# SensorControl.net
KiCad netlist of a schematic drawn in Altium Designer
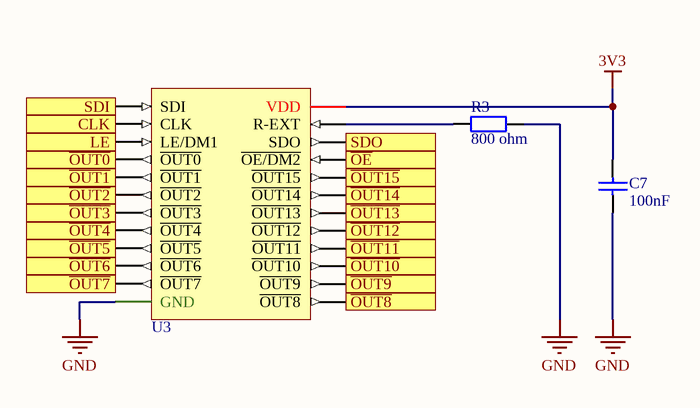
[diagram p0: SensorControl.SchDoc]

(export (version "E")
  (design (tool "Eeschema 10.0.6"))
  (components
    (comp (ref "C7")
      (value "100nF")
      (footprint "FP_0805_CAP_085")
      (description "Capacitor")
      (fields (field (name "TOLERANCE") "+80%/-20%") (field (name "VOLTAGE") "25V"))
      (libsource (lib "hallglib") (part "CAP 100nF"))
    )
    (comp (ref "R3")
      (value "CRCW0805806RFKEA")
      (footprint "0805-W")
      (description "RES, THICK FILM, 806R, 1%, 0.125W, 0805")
      (fields (field (name "RESISTANCE") "800 ohm"))
      (libsource (lib "RobonAUT") (part "CRCW0805806RFKEA"))
    )
    (comp (ref "U3")
      (value "STP16CP05TTR")
      (footprint "24-Pin TSSOP")
      (description "Led Driver, 16 Outputs, Constant Current, 3V-5.5V in, 30MHz switch, 20V/100mA out, TSSOP-24")
      (libsource (lib "RobonAUT") (part "STP16CP05TTR"))
    )
  )
  (nets
    (net (code "1") (name "/CLK") (class "Default")
      (node (ref "U3") (pin "3") (pinfunction "CLK_3") (pintype "input"))
    )
    (net (code "2") (name "/LE") (class "Default")
      (node (ref "U3") (pin "4") (pinfunction "LE/DM1_4") (pintype "input"))
    )
    (net (code "3") (name "/SDI") (class "Default")
      (node (ref "U3") (pin "2") (pinfunction "SDI_2") (pintype "input"))
    )
    (net (code "4") (name "/SDO") (class "Default")
      (node (ref "U3") (pin "22") (pinfunction "SDO_22") (pintype "output"))
    )
    (net (code "5") (name "/~{OE}") (class "Default")
      (node (ref "U3") (pin "21") (pinfunction "~{OE/DM2}_21") (pintype "input"))
    )
    (net (code "6") (name "/~{OUT0}") (class "Default")
      (node (ref "U3") (pin "5") (pinfunction "~{OUT0}_5") (pintype "output"))
    )
    (net (code "7") (name "/~{OUT1}") (class "Default")
      (node (ref "U3") (pin "6") (pinfunction "~{OUT1}_6") (pintype "output"))
    )
    (net (code "8") (name "/~{OUT2}") (class "Default")
      (node (ref "U3") (pin "7") (pinfunction "~{OUT2}_7") (pintype "output"))
    )
    (net (code "9") (name "/~{OUT3}") (class "Default")
      (node (ref "U3") (pin "8") (pinfunction "~{OUT3}_8") (pintype "output"))
    )
    (net (code "10") (name "/~{OUT4}") (class "Default")
      (node (ref "U3") (pin "9") (pinfunction "~{OUT4}_9") (pintype "output"))
    )
    (net (code "11") (name "/~{OUT5}") (class "Default")
      (node (ref "U3") (pin "10") (pinfunction "~{OUT5}_10") (pintype "output"))
    )
    (net (code "12") (name "/~{OUT6}") (class "Default")
      (node (ref "U3") (pin "11") (pinfunction "~{OUT6}_11") (pintype "output"))
    )
    (net (code "13") (name "/~{OUT7}") (class "Default")
      (node (ref "U3") (pin "12") (pinfunction "~{OUT7}_12") (pintype "output"))
    )
    (net (code "14") (name "/~{OUT8}") (class "Default")
      (node (ref "U3") (pin "13") (pinfunction "~{OUT8}_13") (pintype "output"))
    )
    (net (code "15") (name "/~{OUT9}") (class "Default")
      (node (ref "U3") (pin "14") (pinfunction "~{OUT9}_14") (pintype "output"))
    )
    (net (code "16") (name "/~{OUT10}") (class "Default")
      (node (ref "U3") (pin "15") (pinfunction "~{OUT10}_15") (pintype "output"))
    )
    (net (code "17") (name "/~{OUT11}") (class "Default")
      (node (ref "U3") (pin "16") (pinfunction "~{OUT11}_16") (pintype "output"))
    )
    (net (code "18") (name "/~{OUT12}") (class "Default")
      (node (ref "U3") (pin "17") (pinfunction "~{OUT12}_17") (pintype "output"))
    )
    (net (code "19") (name "/~{OUT13}") (class "Default")
      (node (ref "U3") (pin "18") (pinfunction "~{OUT13}_18") (pintype "output"))
    )
    (net (code "20") (name "/~{OUT14}") (class "Default")
      (node (ref "U3") (pin "19") (pinfunction "~{OUT14}_19") (pintype "output"))
    )
    (net (code "21") (name "/~{OUT15}") (class "Default")
      (node (ref "U3") (pin "20") (pinfunction "~{OUT15}_20") (pintype "output"))
    )
    (net (code "22") (name "3V3") (class "Default")
      (node (ref "C7") (pin "2") (pinfunction "2_2") (pintype "passive"))
      (node (ref "U3") (pin "24") (pinfunction "VDD_24") (pintype "power_in"))
    )
    (net (code "23") (name "GND") (class "Default")
      (node (ref "C7") (pin "1") (pinfunction "1_1") (pintype "passive"))
      (node (ref "R3") (pin "2") (pinfunction "2_2") (pintype "passive"))
      (node (ref "U3") (pin "1") (pinfunction "GND_1") (pintype "power_in"))
    )
    (net (code "24") (name "Net-(U3-R-EXT)") (class "Default")
      (node (ref "R3") (pin "1") (pinfunction "1_1") (pintype "passive"))
      (node (ref "U3") (pin "23") (pinfunction "R-EXT_23") (pintype "input"))
    )
  )
)
